# yard-ice-cpu.net
KiCad netlist of a schematic drawn in Altium Designer
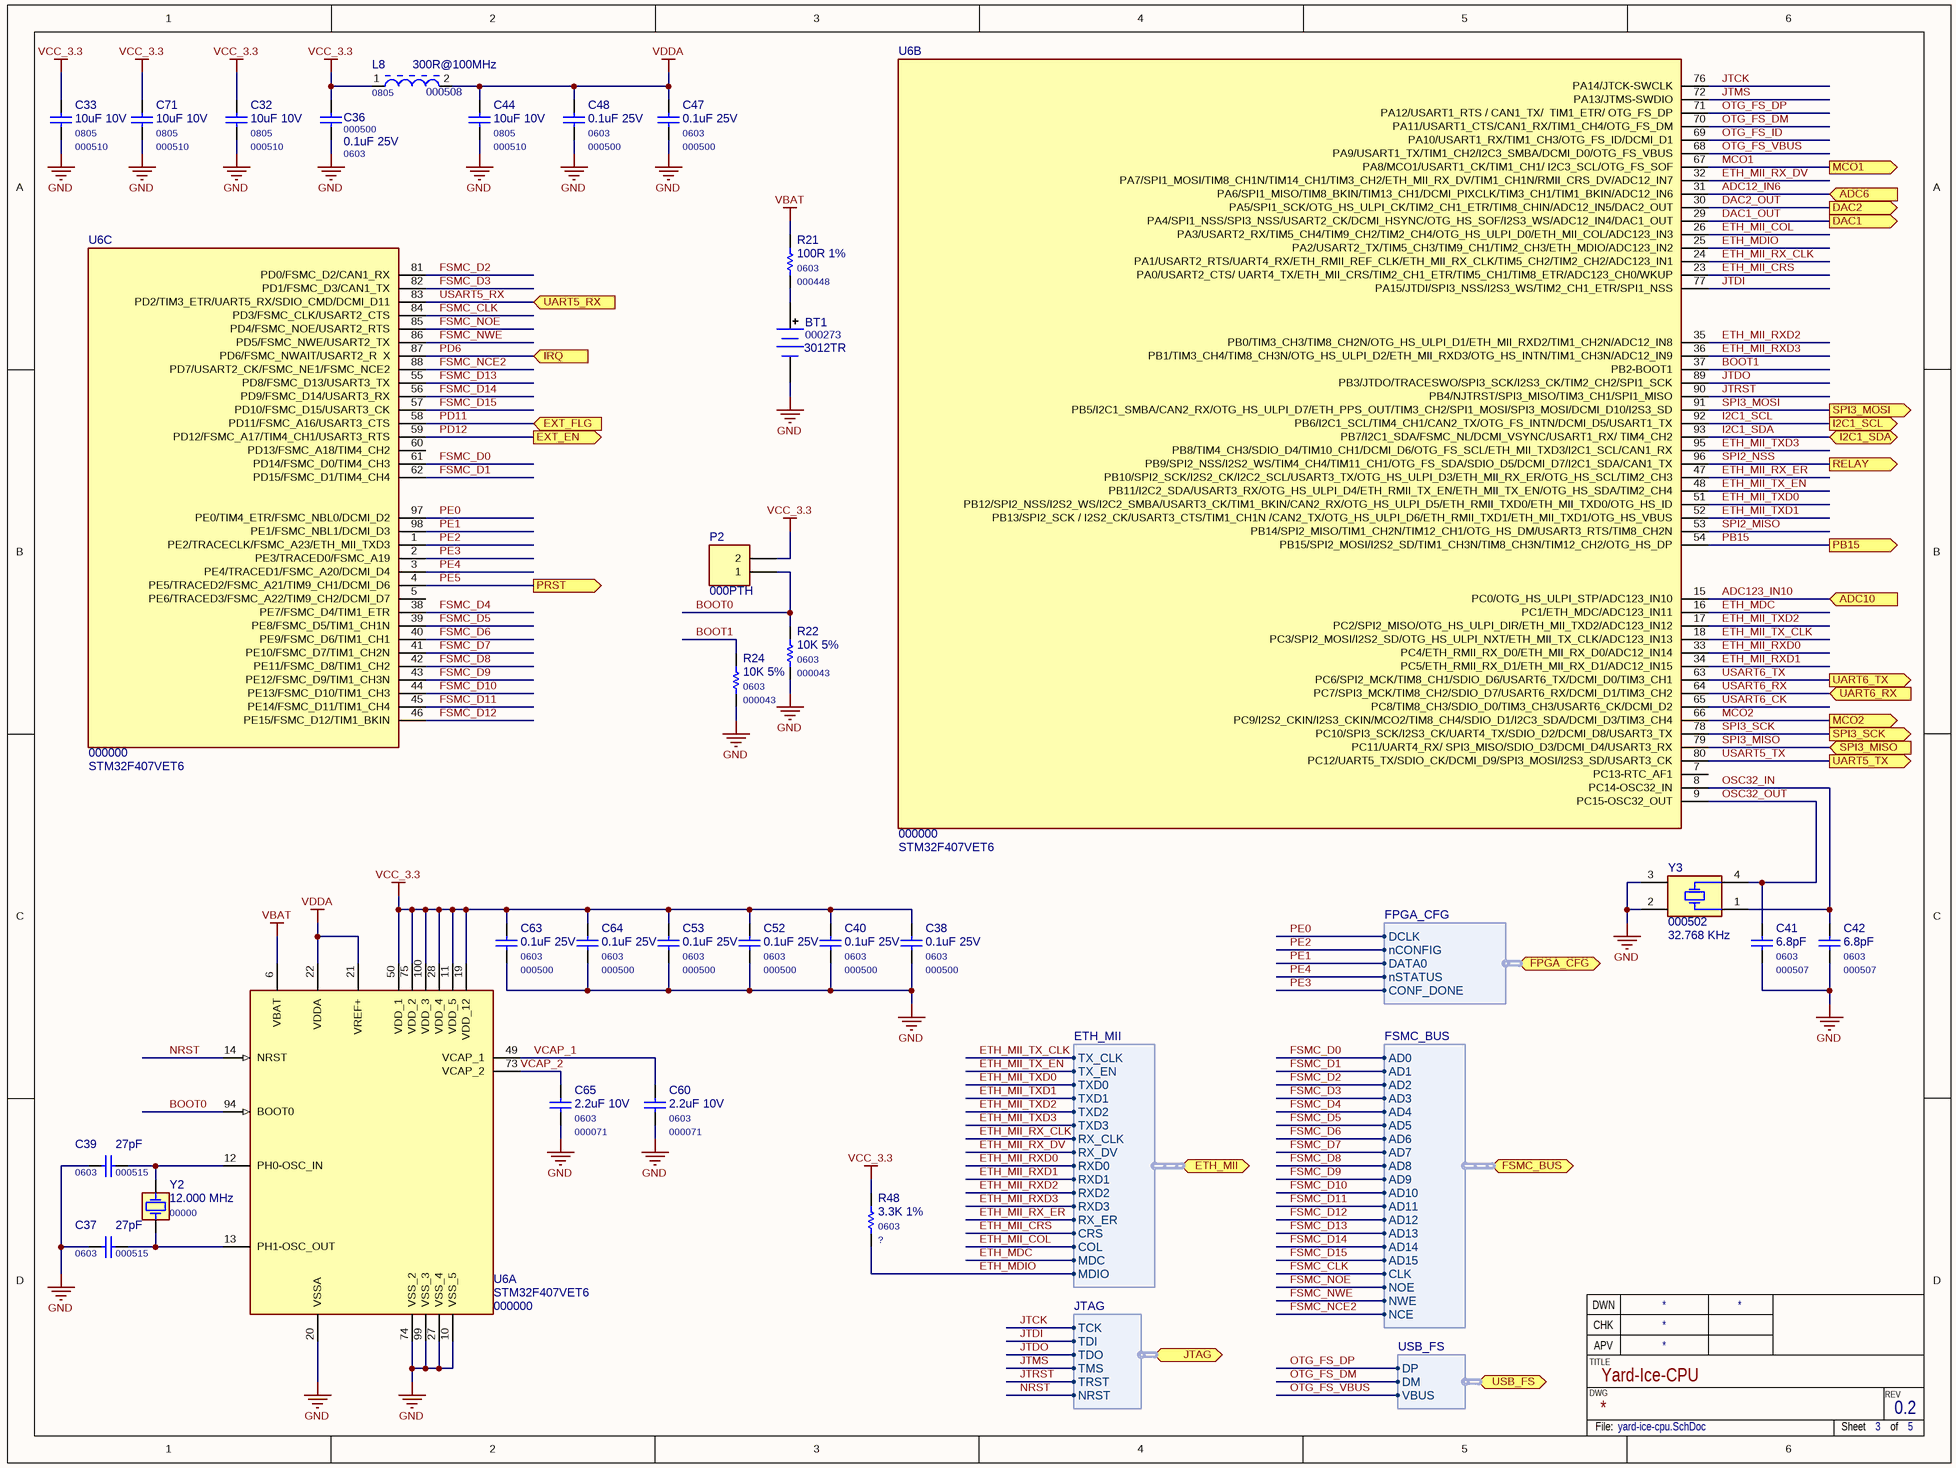
[diagram p0: yard-ice-cpu.SchDoc]

(export (version "E")
  (design (tool "Eeschema 10.0.6"))
  (components
    (comp (ref "BT1")
      (value "000273")
      (footprint "3012TR")
      (description "CR1620 SMD Battery Holder")
      (fields (field (name "MF") "Kestone") (field (name "ALTIUM_VALUE") "3012TR"))
      (libsource (lib "discrete-sm") (part "3012TR"))
    )
    (comp (ref "C32")
      (value "TDK")
      (footprint "C0805M")
      (description "SMD Ceramic Chip Capacitor - 0805 - X7R")
      (fields (field (name "ALTIUM_VALUE") "10uF 10V") (field (name "PACKAGE") "0805"))
      (libsource (lib "discrete-sm") (part "C0805"))
    )
    (comp (ref "C33")
      (value "TDK")
      (footprint "C0805M")
      (description "SMD Ceramic Chip Capacitor - 0805 - X7R")
      (fields (field (name "ALTIUM_VALUE") "10uF 10V") (field (name "PACKAGE") "0805"))
      (libsource (lib "discrete-sm") (part "C0805"))
    )
    (comp (ref "C36")
      (value "000500")
      (footprint "C0603M")
      (description "SMD Ceramic Chip Capacitor - 0603 - X7R")
      (fields
        (field (name "ALTIUM_VALUE") "0.1uF 25V")
        (field (name "PACKAGE") "0603")
        (field (name "MF") "TDK")
      )
      (libsource (lib "discrete-sm") (part "C0603"))
    )
    (comp (ref "C37")
      (value "000515")
      (footprint "C0603M")
      (description "SMD Ceramic Chip Capacitor - 0603")
      (fields (field (name "ALTIUM_VALUE") "27pF") (field (name "PACKAGE") "0603"))
      (libsource (lib "discrete-sm") (part "C0603"))
    )
    (comp (ref "C38")
      (value "000500")
      (footprint "C0603M")
      (description "SMD Ceramic Chip Capacitor - 0603 - X7R")
      (fields
        (field (name "ALTIUM_VALUE") "0.1uF 25V")
        (field (name "PACKAGE") "0603")
        (field (name "MF") "TDK")
      )
      (libsource (lib "discrete-sm") (part "C0603"))
    )
    (comp (ref "C39")
      (value "000515")
      (footprint "C0603M")
      (description "SMD Ceramic Chip Capacitor - 0603")
      (fields (field (name "ALTIUM_VALUE") "27pF") (field (name "PACKAGE") "0603"))
      (libsource (lib "discrete-sm") (part "C0603"))
    )
    (comp (ref "C40")
      (value "000500")
      (footprint "C0603M")
      (description "SMD Ceramic Chip Capacitor - 0603 - X7R")
      (fields
        (field (name "ALTIUM_VALUE") "0.1uF 25V")
        (field (name "PACKAGE") "0603")
        (field (name "MF") "TDK")
      )
      (libsource (lib "discrete-sm") (part "C0603"))
    )
    (comp (ref "C41")
      (value "000507")
      (footprint "C0603M")
      (description "SMD Ceramic Chip Capacitor - 0603")
      (fields (field (name "ALTIUM_VALUE") "6.8pF") (field (name "PACKAGE") "0603"))
      (libsource (lib "discrete-sm") (part "C0603"))
    )
    (comp (ref "C42")
      (value "000507")
      (footprint "C0603M")
      (description "SMD Ceramic Chip Capacitor - 0603")
      (fields (field (name "ALTIUM_VALUE") "6.8pF") (field (name "PACKAGE") "0603"))
      (libsource (lib "discrete-sm") (part "C0603"))
    )
    (comp (ref "C44")
      (value "000510")
      (footprint "C0805M")
      (description "SMD Ceramic Chip Capacitor - 0805 - X7R")
      (fields
        (field (name "ALTIUM_VALUE") "10uF 10V")
        (field (name "PACKAGE") "0805")
        (field (name "MF") "TDK")
      )
      (libsource (lib "discrete-sm") (part "C0805"))
    )
    (comp (ref "C47")
      (value "000500")
      (footprint "C0603M")
      (description "SMD Ceramic Chip Capacitor - 0603 - X7R")
      (fields
        (field (name "ALTIUM_VALUE") "0.1uF 25V")
        (field (name "PACKAGE") "0603")
        (field (name "MF") "TDK")
      )
      (libsource (lib "discrete-sm") (part "C0603"))
    )
    (comp (ref "C48")
      (value "000500")
      (footprint "C0603M")
      (description "SMD Ceramic Chip Capacitor - 0603 - X7R")
      (fields
        (field (name "ALTIUM_VALUE") "0.1uF 25V")
        (field (name "PACKAGE") "0603")
        (field (name "MF") "TDK")
      )
      (libsource (lib "discrete-sm") (part "C0603"))
    )
    (comp (ref "C52")
      (value "000500")
      (footprint "C0603M")
      (description "SMD Ceramic Chip Capacitor - 0603 - X7R")
      (fields
        (field (name "ALTIUM_VALUE") "0.1uF 25V")
        (field (name "PACKAGE") "0603")
        (field (name "MF") "TDK")
      )
      (libsource (lib "discrete-sm") (part "C0603"))
    )
    (comp (ref "C53")
      (value "000500")
      (footprint "C0603M")
      (description "SMD Ceramic Chip Capacitor - 0603 - X7R")
      (fields
        (field (name "ALTIUM_VALUE") "0.1uF 25V")
        (field (name "PACKAGE") "0603")
        (field (name "MF") "TDK")
      )
      (libsource (lib "discrete-sm") (part "C0603"))
    )
    (comp (ref "C60")
      (value "000071")
      (footprint "C0603M")
      (description "SMD Ceramic Chip Capacitor - 0603 - X7R")
      (fields
        (field (name "ALTIUM_VALUE") "2.2uF 10V")
        (field (name "PACKAGE") "0603")
        (field (name "MF") "Taiyo Yuden")
      )
      (libsource (lib "discrete-sm") (part "C0603"))
    )
    (comp (ref "C63")
      (value "000500")
      (footprint "C0603M")
      (description "SMD Ceramic Chip Capacitor - 0603 - X7R")
      (fields
        (field (name "ALTIUM_VALUE") "0.1uF 25V")
        (field (name "PACKAGE") "0603")
        (field (name "MF") "TDK")
      )
      (libsource (lib "discrete-sm") (part "C0603"))
    )
    (comp (ref "C64")
      (value "000500")
      (footprint "C0603M")
      (description "SMD Ceramic Chip Capacitor - 0603 - X7R")
      (fields
        (field (name "ALTIUM_VALUE") "0.1uF 25V")
        (field (name "PACKAGE") "0603")
        (field (name "MF") "TDK")
      )
      (libsource (lib "discrete-sm") (part "C0603"))
    )
    (comp (ref "C65")
      (value "000071")
      (footprint "C0603M")
      (description "SMD Ceramic Chip Capacitor - 0603 - X7R")
      (fields
        (field (name "ALTIUM_VALUE") "2.2uF 10V")
        (field (name "PACKAGE") "0603")
        (field (name "MF") "Taiyo Yuden")
      )
      (libsource (lib "discrete-sm") (part "C0603"))
    )
    (comp (ref "C71")
      (value "TDK")
      (footprint "C0805M")
      (description "SMD Ceramic Chip Capacitor - 0805 - X7R")
      (fields (field (name "ALTIUM_VALUE") "10uF 10V") (field (name "PACKAGE") "0805"))
      (libsource (lib "discrete-sm") (part "C0805"))
    )
    (comp (ref "L8")
      (value "000508")
      (footprint "L0805M")
      (description "SMD Ferrite Bead 0805")
      (fields
        (field (name "ALTIUM_VALUE") "300R@100MHz")
        (field (name "PACKAGE") "0805")
        (field (name "MF") "TDK")
      )
      (libsource (lib "discrete-sm") (part "L0805"))
    )
    (comp (ref "P2")
      (value "000PTH")
      (footprint "TSW-102-07-G-S")
      (description "Header, 2-Pin")
      (libsource (lib "samtec-board-to-board") (part "Header 2"))
    )
    (comp (ref "R21")
      (value "000448")
      (footprint "R0603M")
      (description "SMD Chip Resistor - 0603")
      (fields (field (name "ALTIUM_VALUE") "100R 1%") (field (name "PACKAGE") "0603"))
      (libsource (lib "discrete-sm") (part "R0603"))
    )
    (comp (ref "R22")
      (value "000043")
      (footprint "R0603M")
      (description "SMD Chip Resistor - 0603")
      (fields (field (name "ALTIUM_VALUE") "10K 5%") (field (name "PACKAGE") "0603"))
      (libsource (lib "discrete-sm") (part "R0603"))
    )
    (comp (ref "R24")
      (value "000043")
      (footprint "R0603M")
      (description "SMD Chip Resistor - 0603")
      (fields (field (name "ALTIUM_VALUE") "10K 5%") (field (name "PACKAGE") "0603"))
      (libsource (lib "discrete-sm") (part "R0603"))
    )
    (comp (ref "R48")
      (value "?")
      (footprint "R0603M")
      (description "SMD Chip Resistor - 0603")
      (fields (field (name "ALTIUM_VALUE") "3.3K 1%") (field (name "PACKAGE") "0603"))
      (libsource (lib "discrete-sm") (part "R0603"))
    )
    (comp (ref "U6")
      (value "000000")
      (footprint "LQFP100")
      (fields (field (name "ALTIUM_VALUE") "STM32F407VET6"))
      (libsource (lib "st") (part "STM32F407VET6"))
    )
    (comp (ref "Y2")
      (value "00000")
      (footprint "ABM3-H")
      (description "Miniature Ceramic SMD Crystal")
      (fields (field (name "MF") "Abracon") (field (name "ALTIUM_VALUE") "12.000 MHz"))
      (libsource (lib "abracon") (part "ABM3"))
    )
    (comp (ref "Y3")
      (value "000502")
      (footprint "ABS25")
      (description "SMD Low Frequency Crystal")
      (fields (field (name "ALTIUM_VALUE") "32.768 KHz") (field (name "MF") "Abracon"))
      (libsource (lib "abracon") (part "ABS25"))
    )
  )
  (nets
    (net (code "6") (name "/ADC12_IN6") (class "Default")
      (node (ref "U6") (pin "31") (pinfunction "PA6/SPI1_MISO/TIM8_BKIN/TIM13_CH1/DCMI_PIXCLK/TIM3_CH1/TIM1_BKIN/ADC12_IN6_31") (pintype "tri_state"))
    )
    (net (code "7") (name "/ADC123_IN10") (class "Default")
      (node (ref "U6") (pin "15") (pinfunction "PC0/OTG_HS_ULPI_STP/ADC123_IN10_15") (pintype "tri_state"))
    )
    (net (code "8") (name "/BOOT0") (class "Default")
      (node (ref "P2") (pin "1") (pinfunction "1_1") (pintype "passive"))
      (node (ref "R22") (pin "2") (pinfunction "2_2") (pintype "passive"))
      (node (ref "U6") (pin "94") (pinfunction "BOOT0_94") (pintype "input"))
    )
    (net (code "9") (name "/BOOT1") (class "Default")
      (node (ref "R24") (pin "2") (pinfunction "2_2") (pintype "passive"))
      (node (ref "U6") (pin "37") (pinfunction "PB2-BOOT1_37") (pintype "tri_state"))
    )
    (net (code "10") (name "/DAC1_OUT") (class "Default")
      (node (ref "U6") (pin "29") (pinfunction "PA4/SPI1_NSS/SPI3_NSS/USART2_CK/DCMI_HSYNC/OTG_HS_SOF/I2S3_WS/ADC12_IN4/DAC1_OUT_29") (pintype "tri_state"))
    )
    (net (code "11") (name "/DAC2_OUT") (class "Default")
      (node (ref "U6") (pin "30") (pinfunction "PA5/SPI1_SCK/OTG_HS_ULPI_CK/TIM2_CH1_ETR/TIM8_CHIN/ADC12_IN5/DAC2_OUT_30") (pintype "tri_state"))
    )
    (net (code "12") (name "/ETH_MDC") (class "Default")
      (node (ref "U6") (pin "16") (pinfunction "PC1/ETH_MDC/ADC123_IN11_16") (pintype "tri_state"))
    )
    (net (code "13") (name "/ETH_MDIO") (class "Default")
      (node (ref "R48") (pin "1") (pinfunction "1_1") (pintype "passive"))
      (node (ref "U6") (pin "25") (pinfunction "PA2/USART2_TX/TIM5_CH3/TIM9_CH1/TIM2_CH3/ETH_MDIO/ADC123_IN2_25") (pintype "tri_state"))
    )
    (net (code "14") (name "/ETH_MII_COL") (class "Default")
      (node (ref "U6") (pin "26") (pinfunction "PA3/USART2_RX/TIM5_CH4/TIM9_CH2/TIM2_CH4/OTG_HS_ULPI_D0/ETH_MII_COL/ADC123_IN3_26") (pintype "tri_state"))
    )
    (net (code "15") (name "/ETH_MII_CRS") (class "Default")
      (node (ref "U6") (pin "23") (pinfunction "PA0/USART2_CTS/_UART4_TX/ETH_MII_CRS/TIM2_CH1_ETR/TIM5_CH1/TIM8_ETR/ADC123_CH0/WKUP_23") (pintype "tri_state"))
    )
    (net (code "16") (name "/ETH_MII_RXD0") (class "Default")
      (node (ref "U6") (pin "33") (pinfunction "PC4/ETH_RMII_RX_D0/ETH_MII_RX_D0/ADC12_IN14_33") (pintype "tri_state"))
    )
    (net (code "17") (name "/ETH_MII_RXD1") (class "Default")
      (node (ref "U6") (pin "34") (pinfunction "PC5/ETH_RMII_RX_D1/ETH_MII_RX_D1/ADC12_IN15_34") (pintype "tri_state"))
    )
    (net (code "18") (name "/ETH_MII_RXD2") (class "Default")
      (node (ref "U6") (pin "35") (pinfunction "PB0/TIM3_CH3/TIM8_CH2N/OTG_HS_ULPI_D1/ETH_MII_RXD2/TIM1_CH2N/ADC12_IN8_35") (pintype "tri_state"))
    )
    (net (code "19") (name "/ETH_MII_RXD3") (class "Default")
      (node (ref "U6") (pin "36") (pinfunction "PB1/TIM3_CH4/TIM8_CH3N/OTG_HS_ULPI_D2/ETH_MII_RXD3/OTG_HS_INTN/TIM1_CH3N/ADC12_IN9_36") (pintype "tri_state"))
    )
    (net (code "20") (name "/ETH_MII_RX_CLK") (class "Default")
      (node (ref "U6") (pin "24") (pinfunction "PA1/USART2_RTS/UART4_RX/ETH_RMII_REF_CLK/ETH_MII_RX_CLK/TIM5_CH2/TIM2_CH2/ADC123_IN1_24") (pintype "tri_state"))
    )
    (net (code "21") (name "/ETH_MII_RX_DV") (class "Default")
      (node (ref "U6") (pin "32") (pinfunction "PA7/SPI1_MOSI/TIM8_CH1N/TIM14_CH1/TIM3_CH2/ETH_MII_RX_DV/TIM1_CH1N/RMII_CRS_DV/ADC12_IN7_32") (pintype "tri_state"))
    )
    (net (code "22") (name "/ETH_MII_RX_ER") (class "Default")
      (node (ref "U6") (pin "47") (pinfunction "PB10/SPI2_SCK/I2S2_CK/I2C2_SCL/USART3_TX/OTG_HS_ULPI_D3/ETH_MII_RX_ER/OTG_HS_SCL/TIM2_CH3_47") (pintype "tri_state"))
    )
    (net (code "23") (name "/ETH_MII_TXD0") (class "Default")
      (node (ref "U6") (pin "51") (pinfunction "PB12/SPI2_NSS/I2S2_WS/I2C2_SMBA/USART3_CK/TIM1_BKIN/CAN2_RX/OTG_HS_ULPI_D5/ETH_RMII_TXD0/ETH_MII_TXD0/OTG_HS_ID_51") (pintype "tri_state"))
    )
    (net (code "24") (name "/ETH_MII_TXD1") (class "Default")
      (node (ref "U6") (pin "52") (pinfunction "PB13/SPI2_SCK_/_I2S2_CK/USART3_CTS/TIM1_CH1N_/CAN2_TX/OTG_HS_ULPI_D6/ETH_RMII_TXD1/ETH_MII_TXD1/OTG_HS_VBUS_52") (pintype "tri_state"))
    )
    (net (code "25") (name "/ETH_MII_TXD2") (class "Default")
      (node (ref "U6") (pin "17") (pinfunction "PC2/SPI2_MISO/OTG_HS_ULPI_DIR/ETH_MII_TXD2/ADC123_IN12_17") (pintype "tri_state"))
    )
    (net (code "26") (name "/ETH_MII_TXD3") (class "Default")
      (node (ref "U6") (pin "95") (pinfunction "PB8/TIM4_CH3/SDIO_D4/TIM10_CH1/DCMI_D6/OTG_FS_SCL/ETH_MII_TXD3/I2C1_SCL/CAN1_RX_95") (pintype "tri_state"))
    )
    (net (code "27") (name "/ETH_MII_TX_CLK") (class "Default")
      (node (ref "U6") (pin "18") (pinfunction "PC3/SPI2_MOSI/I2S2_SD/OTG_HS_ULPI_NXT/ETH_MII_TX_CLK/ADC123_IN13_18") (pintype "tri_state"))
    )
    (net (code "28") (name "/ETH_MII_TX_EN") (class "Default")
      (node (ref "U6") (pin "48") (pinfunction "PB11/I2C2_SDA/USART3_RX/OTG_HS_ULPI_D4/ETH_RMII_TX_EN/ETH_MII_TX_EN/OTG_HS_SDA/TIM2_CH4_48") (pintype "tri_state"))
    )
    (net (code "29") (name "/FSMC_CLK") (class "Default")
      (node (ref "U6") (pin "84") (pinfunction "PD3/FSMC_CLK/USART2_CTS_84") (pintype "tri_state"))
    )
    (net (code "30") (name "/FSMC_D0") (class "Default")
      (node (ref "U6") (pin "61") (pinfunction "PD14/FSMC_D0/TIM4_CH3_61") (pintype "tri_state"))
    )
    (net (code "31") (name "/FSMC_D1") (class "Default")
      (node (ref "U6") (pin "62") (pinfunction "PD15/FSMC_D1/TIM4_CH4_62") (pintype "tri_state"))
    )
    (net (code "32") (name "/FSMC_D2") (class "Default")
      (node (ref "U6") (pin "81") (pinfunction "PD0/FSMC_D2/CAN1_RX_81") (pintype "tri_state"))
    )
    (net (code "33") (name "/FSMC_D3") (class "Default")
      (node (ref "U6") (pin "82") (pinfunction "PD1/FSMC_D3/CAN1_TX_82") (pintype "tri_state"))
    )
    (net (code "34") (name "/FSMC_D4") (class "Default")
      (node (ref "U6") (pin "38") (pinfunction "PE7/FSMC_D4/TIM1_ETR_38") (pintype "tri_state"))
    )
    (net (code "35") (name "/FSMC_D5") (class "Default")
      (node (ref "U6") (pin "39") (pinfunction "PE8/FSMC_D5/TIM1_CH1N_39") (pintype "tri_state"))
    )
    (net (code "36") (name "/FSMC_D6") (class "Default")
      (node (ref "U6") (pin "40") (pinfunction "PE9/FSMC_D6/TIM1_CH1_40") (pintype "tri_state"))
    )
    (net (code "37") (name "/FSMC_D7") (class "Default")
      (node (ref "U6") (pin "41") (pinfunction "PE10/FSMC_D7/TIM1_CH2N_41") (pintype "tri_state"))
    )
    (net (code "38") (name "/FSMC_D8") (class "Default")
      (node (ref "U6") (pin "42") (pinfunction "PE11/FSMC_D8/TIM1_CH2_42") (pintype "tri_state"))
    )
    (net (code "39") (name "/FSMC_D9") (class "Default")
      (node (ref "U6") (pin "43") (pinfunction "PE12/FSMC_D9/TIM1_CH3N_43") (pintype "tri_state"))
    )
    (net (code "40") (name "/FSMC_D10") (class "Default")
      (node (ref "U6") (pin "44") (pinfunction "PE13/FSMC_D10/TIM1_CH3_44") (pintype "tri_state"))
    )
    (net (code "41") (name "/FSMC_D11") (class "Default")
      (node (ref "U6") (pin "45") (pinfunction "PE14/FSMC_D11/TIM1_CH4_45") (pintype "tri_state"))
    )
    (net (code "42") (name "/FSMC_D12") (class "Default")
      (node (ref "U6") (pin "46") (pinfunction "PE15/FSMC_D12/TIM1_BKIN_46") (pintype "tri_state"))
    )
    (net (code "43") (name "/FSMC_D13") (class "Default")
      (node (ref "U6") (pin "55") (pinfunction "PD8/FSMC_D13/USART3_TX_55") (pintype "tri_state"))
    )
    (net (code "44") (name "/FSMC_D14") (class "Default")
      (node (ref "U6") (pin "56") (pinfunction "PD9/FSMC_D14/USART3_RX_56") (pintype "tri_state"))
    )
    (net (code "45") (name "/FSMC_D15") (class "Default")
      (node (ref "U6") (pin "57") (pinfunction "PD10/FSMC_D15/USART3_CK_57") (pintype "tri_state"))
    )
    (net (code "46") (name "/FSMC_NCE2") (class "Default")
      (node (ref "U6") (pin "88") (pinfunction "PD7/USART2_CK/FSMC_NE1/FSMC_NCE2_88") (pintype "tri_state"))
    )
    (net (code "47") (name "/FSMC_NOE") (class "Default")
      (node (ref "U6") (pin "85") (pinfunction "PD4/FSMC_NOE/USART2_RTS_85") (pintype "tri_state"))
    )
    (net (code "48") (name "/FSMC_NWE") (class "Default")
      (node (ref "U6") (pin "86") (pinfunction "PD5/FSMC_NWE/USART2_TX_86") (pintype "tri_state"))
    )
    (net (code "49") (name "/I2C1_SCL") (class "Default")
      (node (ref "U6") (pin "92") (pinfunction "PB6/I2C1_SCL/TIM4_CH1/CAN2_TX/OTG_FS_INTN/DCMI_D5/USART1_TX_92") (pintype "tri_state"))
    )
    (net (code "50") (name "/I2C1_SDA") (class "Default")
      (node (ref "U6") (pin "93") (pinfunction "PB7/I2C1_SDA/FSMC_NL/DCMI_VSYNC/USART1_RX/_TIM4_CH2_93") (pintype "tri_state"))
    )
    (net (code "51") (name "/JTCK") (class "Default")
      (node (ref "U6") (pin "76") (pinfunction "PA14/JTCK-SWCLK_76") (pintype "tri_state"))
    )
    (net (code "52") (name "/JTDI") (class "Default")
      (node (ref "U6") (pin "77") (pinfunction "PA15/JTDI/SPI3_NSS/I2S3_WS/TIM2_CH1_ETR/SPI1_NSS_77") (pintype "tri_state"))
    )
    (net (code "53") (name "/JTDO") (class "Default")
      (node (ref "U6") (pin "89") (pinfunction "PB3/JTDO/TRACESWO/SPI3_SCK/I2S3_CK/TIM2_CH2/SPI1_SCK_89") (pintype "tri_state"))
    )
    (net (code "54") (name "/JTMS") (class "Default")
      (node (ref "U6") (pin "72") (pinfunction "PA13/JTMS-SWDIO_72") (pintype "tri_state"))
    )
    (net (code "55") (name "/JTRST") (class "Default")
      (node (ref "U6") (pin "90") (pinfunction "PB4/NJTRST/SPI3_MISO/TIM3_CH1/SPI1_MISO_90") (pintype "tri_state"))
    )
    (net (code "56") (name "/MCO1") (class "Default")
      (node (ref "U6") (pin "67") (pinfunction "PA8/MCO1/USART1_CK/TIM1_CH1/_I2C3_SCL/OTG_FS_SOF_67") (pintype "tri_state"))
    )
    (net (code "57") (name "/MCO2") (class "Default")
      (node (ref "U6") (pin "66") (pinfunction "PC9/I2S2_CKIN/I2S3_CKIN/MCO2/TIM8_CH4/SDIO_D1/I2C3_SDA/DCMI_D3/TIM3_CH4_66") (pintype "tri_state"))
    )
    (net (code "58") (name "/NRST") (class "Default")
      (node (ref "U6") (pin "14") (pinfunction "NRST_14") (pintype "input"))
    )
    (net (code "59") (name "/OSC32_IN") (class "Default")
      (node (ref "C42") (pin "2") (pinfunction "2_2") (pintype "passive"))
      (node (ref "U6") (pin "8") (pinfunction "PC14-OSC32_IN_8") (pintype "tri_state"))
      (node (ref "Y3") (pin "1") (pinfunction "1_1") (pintype "passive"))
    )
    (net (code "60") (name "/OSC32_OUT") (class "Default")
      (node (ref "C41") (pin "2") (pinfunction "2_2") (pintype "passive"))
      (node (ref "U6") (pin "9") (pinfunction "PC15-OSC32_OUT_9") (pintype "tri_state"))
      (node (ref "Y3") (pin "4") (pinfunction "4_4") (pintype "passive"))
    )
    (net (code "61") (name "/OTG_FS_DM") (class "Default")
      (node (ref "U6") (pin "70") (pinfunction "PA11/USART1_CTS/CAN1_RX/TIM1_CH4/OTG_FS_DM_70") (pintype "tri_state"))
    )
    (net (code "62") (name "/OTG_FS_DP") (class "Default")
      (node (ref "U6") (pin "71") (pinfunction "PA12/USART1_RTS_/_CAN1_TX/__TIM1_ETR/_OTG_FS_DP_71") (pintype "tri_state"))
    )
    (net (code "63") (name "/OTG_FS_ID") (class "Default")
      (node (ref "U6") (pin "69") (pinfunction "PA10/USART1_RX/TIM1_CH3/OTG_FS_ID/DCMI_D1_69") (pintype "tri_state"))
    )
    (net (code "64") (name "/OTG_FS_VBUS") (class "Default")
      (node (ref "U6") (pin "68") (pinfunction "PA9/USART1_TX/TIM1_CH2/I2C3_SMBA/DCMI_D0/OTG_FS_VBUS_68") (pintype "tri_state"))
    )
    (net (code "65") (name "/PB15") (class "Default")
      (node (ref "U6") (pin "54") (pinfunction "PB15/SPI2_MOSI/I2S2_SD/TIM1_CH3N/TIM8_CH3N/TIM12_CH2/OTG_HS_DP_54") (pintype "tri_state"))
    )
    (net (code "66") (name "/PD6") (class "Default")
      (node (ref "U6") (pin "87") (pinfunction "PD6/FSMC_NWAIT/USART2_R__X_87") (pintype "tri_state"))
    )
    (net (code "67") (name "/PD11") (class "Default")
      (node (ref "U6") (pin "58") (pinfunction "PD11/FSMC_A16/USART3_CTS_58") (pintype "tri_state"))
    )
    (net (code "68") (name "/PD12") (class "Default")
      (node (ref "U6") (pin "59") (pinfunction "PD12/FSMC_A17/TIM4_CH1/USART3_RTS_59") (pintype "tri_state"))
    )
    (net (code "69") (name "/PE0") (class "Default")
      (node (ref "U6") (pin "97") (pinfunction "PE0/TIM4_ETR/FSMC_NBL0/DCMI_D2_97") (pintype "tri_state"))
    )
    (net (code "70") (name "/PE1") (class "Default")
      (node (ref "U6") (pin "98") (pinfunction "PE1/FSMC_NBL1/DCMI_D3_98") (pintype "tri_state"))
    )
    (net (code "71") (name "/PE2") (class "Default")
      (node (ref "U6") (pin "1") (pinfunction "PE2/TRACECLK/FSMC_A23/ETH_MII_TXD3_1") (pintype "tri_state"))
    )
    (net (code "72") (name "/PE3") (class "Default")
      (node (ref "U6") (pin "2") (pinfunction "PE3/TRACED0/FSMC_A19_2") (pintype "tri_state"))
    )
    (net (code "73") (name "/PE4") (class "Default")
      (node (ref "U6") (pin "3") (pinfunction "PE4/TRACED1/FSMC_A20/DCMI_D4_3") (pintype "tri_state"))
    )
    (net (code "74") (name "/PE5") (class "Default")
      (node (ref "U6") (pin "4") (pinfunction "PE5/TRACED2/FSMC_A21/TIM9_CH1/DCMI_D6_4") (pintype "tri_state"))
    )
    (net (code "75") (name "/SPI2_MISO") (class "Default")
      (node (ref "U6") (pin "53") (pinfunction "PB14/SPI2_MISO/TIM1_CH2N/TIM12_CH1/OTG_HS_DM/USART3_RTS/TIM8_CH2N_53") (pintype "tri_state"))
    )
    (net (code "76") (name "/SPI2_NSS") (class "Default")
      (node (ref "U6") (pin "96") (pinfunction "PB9/SPI2_NSS/I2S2_WS/TIM4_CH4/TIM11_CH1/OTG_FS_SDA/SDIO_D5/DCMI_D7/I2C1_SDA/CAN1_TX_96") (pintype "tri_state"))
    )
    (net (code "77") (name "/SPI3_MISO") (class "Default")
      (node (ref "U6") (pin "79") (pinfunction "PC11/UART4_RX/_SPI3_MISO/SDIO_D3/DCMI_D4/USART3_RX_79") (pintype "tri_state"))
    )
    (net (code "78") (name "/SPI3_MOSI") (class "Default")
      (node (ref "U6") (pin "91") (pinfunction "PB5/I2C1_SMBA/CAN2_RX/OTG_HS_ULPI_D7/ETH_PPS_OUT/TIM3_CH2/SPI1_MOSI/SPI3_MOSI/DCMI_D10/I2S3_SD_91") (pintype "tri_state"))
    )
    (net (code "79") (name "/SPI3_SCK") (class "Default")
      (node (ref "U6") (pin "78") (pinfunction "PC10/SPI3_SCK/I2S3_CK/UART4_TX/SDIO_D2/DCMI_D8/USART3_TX_78") (pintype "tri_state"))
    )
    (net (code "80") (name "/USART5_RX") (class "Default")
      (node (ref "U6") (pin "83") (pinfunction "PD2/TIM3_ETR/UART5_RX/SDIO_CMD/DCMI_D11_83") (pintype "tri_state"))
    )
    (net (code "81") (name "/USART5_TX") (class "Default")
      (node (ref "U6") (pin "80") (pinfunction "PC12/UART5_TX/SDIO_CK/DCMI_D9/SPI3_MOSI/I2S3_SD/USART3_CK_80") (pintype "tri_state"))
    )
    (net (code "82") (name "/USART6_CK") (class "Default")
      (node (ref "U6") (pin "65") (pinfunction "PC8/TIM8_CH3/SDIO_D0/TIM3_CH3/USART6_CK/DCMI_D2_65") (pintype "tri_state"))
    )
    (net (code "83") (name "/USART6_RX") (class "Default")
      (node (ref "U6") (pin "64") (pinfunction "PC7/SPI3_MCK/TIM8_CH2/SDIO_D7/USART6_RX/DCMI_D1/TIM3_CH2_64") (pintype "tri_state"))
    )
    (net (code "84") (name "/USART6_TX") (class "Default")
      (node (ref "U6") (pin "63") (pinfunction "PC6/SPI2_MCK/TIM8_CH1/SDIO_D6/USART6_TX/DCMI_D0/TIM3_CH1_63") (pintype "tri_state"))
    )
    (net (code "85") (name "/VCAP_1") (class "Default")
      (node (ref "C60") (pin "1") (pinfunction "1_1") (pintype "passive"))
      (node (ref "U6") (pin "49") (pinfunction "VCAP_1_49") (pintype "power_in"))
    )
    (net (code "86") (name "/VCAP_2") (class "Default")
      (node (ref "C65") (pin "1") (pinfunction "1_1") (pintype "passive"))
      (node (ref "U6") (pin "73") (pinfunction "VCAP_2_73") (pintype "power_in"))
    )
    (net (code "92") (name "GND") (class "Default")
      (node (ref "BT1") (pin "2") (pinfunction "-_2") (pintype "passive"))
      (node (ref "C32") (pin "2") (pinfunction "2_2") (pintype "passive"))
      (node (ref "C33") (pin "2") (pinfunction "2_2") (pintype "passive"))
      (node (ref "C36") (pin "2") (pinfunction "2_2") (pintype "passive"))
      (node (ref "C37") (pin "1") (pinfunction "1_1") (pintype "passive"))
      (node (ref "C38") (pin "2") (pinfunction "2_2") (pintype "passive"))
      (node (ref "C39") (pin "1") (pinfunction "1_1") (pintype "passive"))
      (node (ref "C40") (pin "2") (pinfunction "2_2") (pintype "passive"))
      (node (ref "C41") (pin "1") (pinfunction "1_1") (pintype "passive"))
      (node (ref "C42") (pin "1") (pinfunction "1_1") (pintype "passive"))
      (node (ref "C44") (pin "2") (pinfunction "2_2") (pintype "passive"))
      (node (ref "C47") (pin "2") (pinfunction "2_2") (pintype "passive"))
      (node (ref "C48") (pin "2") (pinfunction "2_2") (pintype "passive"))
      (node (ref "C52") (pin "2") (pinfunction "2_2") (pintype "passive"))
      (node (ref "C53") (pin "2") (pinfunction "2_2") (pintype "passive"))
      (node (ref "C60") (pin "2") (pinfunction "2_2") (pintype "passive"))
      (node (ref "C63") (pin "2") (pinfunction "2_2") (pintype "passive"))
      (node (ref "C64") (pin "2") (pinfunction "2_2") (pintype "passive"))
      (node (ref "C65") (pin "2") (pinfunction "2_2") (pintype "passive"))
      (node (ref "C71") (pin "2") (pinfunction "2_2") (pintype "passive"))
      (node (ref "R22") (pin "1") (pinfunction "1_1") (pintype "passive"))
      (node (ref "R24") (pin "1") (pinfunction "1_1") (pintype "passive"))
      (node (ref "U6") (pin "10") (pinfunction "VSS_5_10") (pintype "power_in"))
      (node (ref "U6") (pin "20") (pinfunction "VSSA_20") (pintype "power_in"))
      (node (ref "U6") (pin "27") (pinfunction "VSS_4_27") (pintype "power_in"))
      (node (ref "U6") (pin "74") (pinfunction "VSS_2_74") (pintype "power_in"))
      (node (ref "U6") (pin "99") (pinfunction "VSS_3_99") (pintype "passive"))
      (node (ref "Y3") (pin "2") (pinfunction "2_2") (pintype "passive"))
      (node (ref "Y3") (pin "3") (pinfunction "3_3") (pintype "passive"))
    )
    (net (code "93") (name "Net-(BT1-+)") (class "Default")
      (node (ref "BT1") (pin "1") (pinfunction "+_1") (pintype "passive"))
      (node (ref "R21") (pin "1") (pinfunction "1_1") (pintype "passive"))
    )
    (net (code "94") (name "Net-(U6A-PH0-OSC_IN)") (class "Default")
      (node (ref "C39") (pin "2") (pinfunction "2_2") (pintype "passive"))
      (node (ref "U6") (pin "12") (pinfunction "PH0-OSC_IN_12") (pintype "tri_state"))
      (node (ref "Y2") (pin "1") (pinfunction "1_1") (pintype "passive"))
    )
    (net (code "95") (name "Net-(U6A-PH1-OSC_OUT)") (class "Default")
      (node (ref "C37") (pin "2") (pinfunction "2_2") (pintype "passive"))
      (node (ref "U6") (pin "13") (pinfunction "PH1-OSC_OUT_13") (pintype "tri_state"))
      (node (ref "Y2") (pin "2") (pinfunction "2_2") (pintype "passive"))
    )
    (net (code "96") (name "VBAT") (class "Default")
      (node (ref "R21") (pin "2") (pinfunction "2_2") (pintype "passive"))
      (node (ref "U6") (pin "6") (pinfunction "VBAT_6") (pintype "power_in"))
    )
    (net (code "97") (name "VCC_3.3") (class "Default")
      (node (ref "C32") (pin "1") (pinfunction "1_1") (pintype "passive"))
      (node (ref "C33") (pin "1") (pinfunction "1_1") (pintype "passive"))
      (node (ref "C36") (pin "1") (pinfunction "1_1") (pintype "passive"))
      (node (ref "C38") (pin "1") (pinfunction "1_1") (pintype "passive"))
      (node (ref "C40") (pin "1") (pinfunction "1_1") (pintype "passive"))
      (node (ref "C52") (pin "1") (pinfunction "1_1") (pintype "passive"))
      (node (ref "C53") (pin "1") (pinfunction "1_1") (pintype "passive"))
      (node (ref "C63") (pin "1") (pinfunction "1_1") (pintype "passive"))
      (node (ref "C64") (pin "1") (pinfunction "1_1") (pintype "passive"))
      (node (ref "C71") (pin "1") (pinfunction "1_1") (pintype "passive"))
      (node (ref "L8") (pin "1") (pinfunction "1_1") (pintype "passive"))
      (node (ref "P2") (pin "2") (pinfunction "2_2") (pintype "passive"))
      (node (ref "R48") (pin "2") (pinfunction "2_2") (pintype "passive"))
      (node (ref "U6") (pin "100") (pinfunction "VDD_3_100") (pintype "power_in"))
      (node (ref "U6") (pin "11") (pinfunction "VDD_5_11") (pintype "power_in"))
      (node (ref "U6") (pin "19") (pinfunction "VDD_12_19") (pintype "power_in"))
      (node (ref "U6") (pin "28") (pinfunction "VDD_4_28") (pintype "power_in"))
      (node (ref "U6") (pin "50") (pinfunction "VDD_1_50") (pintype "power_in"))
      (node (ref "U6") (pin "75") (pinfunction "VDD_2_75") (pintype "power_in"))
    )
    (net (code "98") (name "VDDA") (class "Default")
      (node (ref "C44") (pin "1") (pinfunction "1_1") (pintype "passive"))
      (node (ref "C47") (pin "1") (pinfunction "1_1") (pintype "passive"))
      (node (ref "C48") (pin "1") (pinfunction "1_1") (pintype "passive"))
      (node (ref "L8") (pin "2") (pinfunction "2_2") (pintype "passive"))
      (node (ref "U6") (pin "21") (pinfunction "VREF+_21") (pintype "power_in"))
      (node (ref "U6") (pin "22") (pinfunction "VDDA_22") (pintype "power_in"))
    )
    (net (code "99") (name "unconnected-(U6B-PC13-RTC_AF1-Pad7)") (class "Default")
      (node (ref "U6") (pin "7") (pinfunction "PC13-RTC_AF1_7") (pintype "tri_state"))
    )
    (net (code "100") (name "unconnected-(U6C-PD13{slash}FSMC_A18{slash}TIM4_CH2-Pad60)") (class "Default")
      (node (ref "U6") (pin "60") (pinfunction "PD13/FSMC_A18/TIM4_CH2_60") (pintype "tri_state"))
    )
    (net (code "101") (name "unconnected-(U6C-PE6{slash}TRACED3{slash}FSMC_A22{slash}TIM9_CH2{slash}DCMI_D7-Pad5)") (class "Default")
      (node (ref "U6") (pin "5") (pinfunction "PE6/TRACED3/FSMC_A22/TIM9_CH2/DCMI_D7_5") (pintype "tri_state"))
    )
  )
)
